# Power88.net
KiCad netlist of a schematic drawn in EAGLE
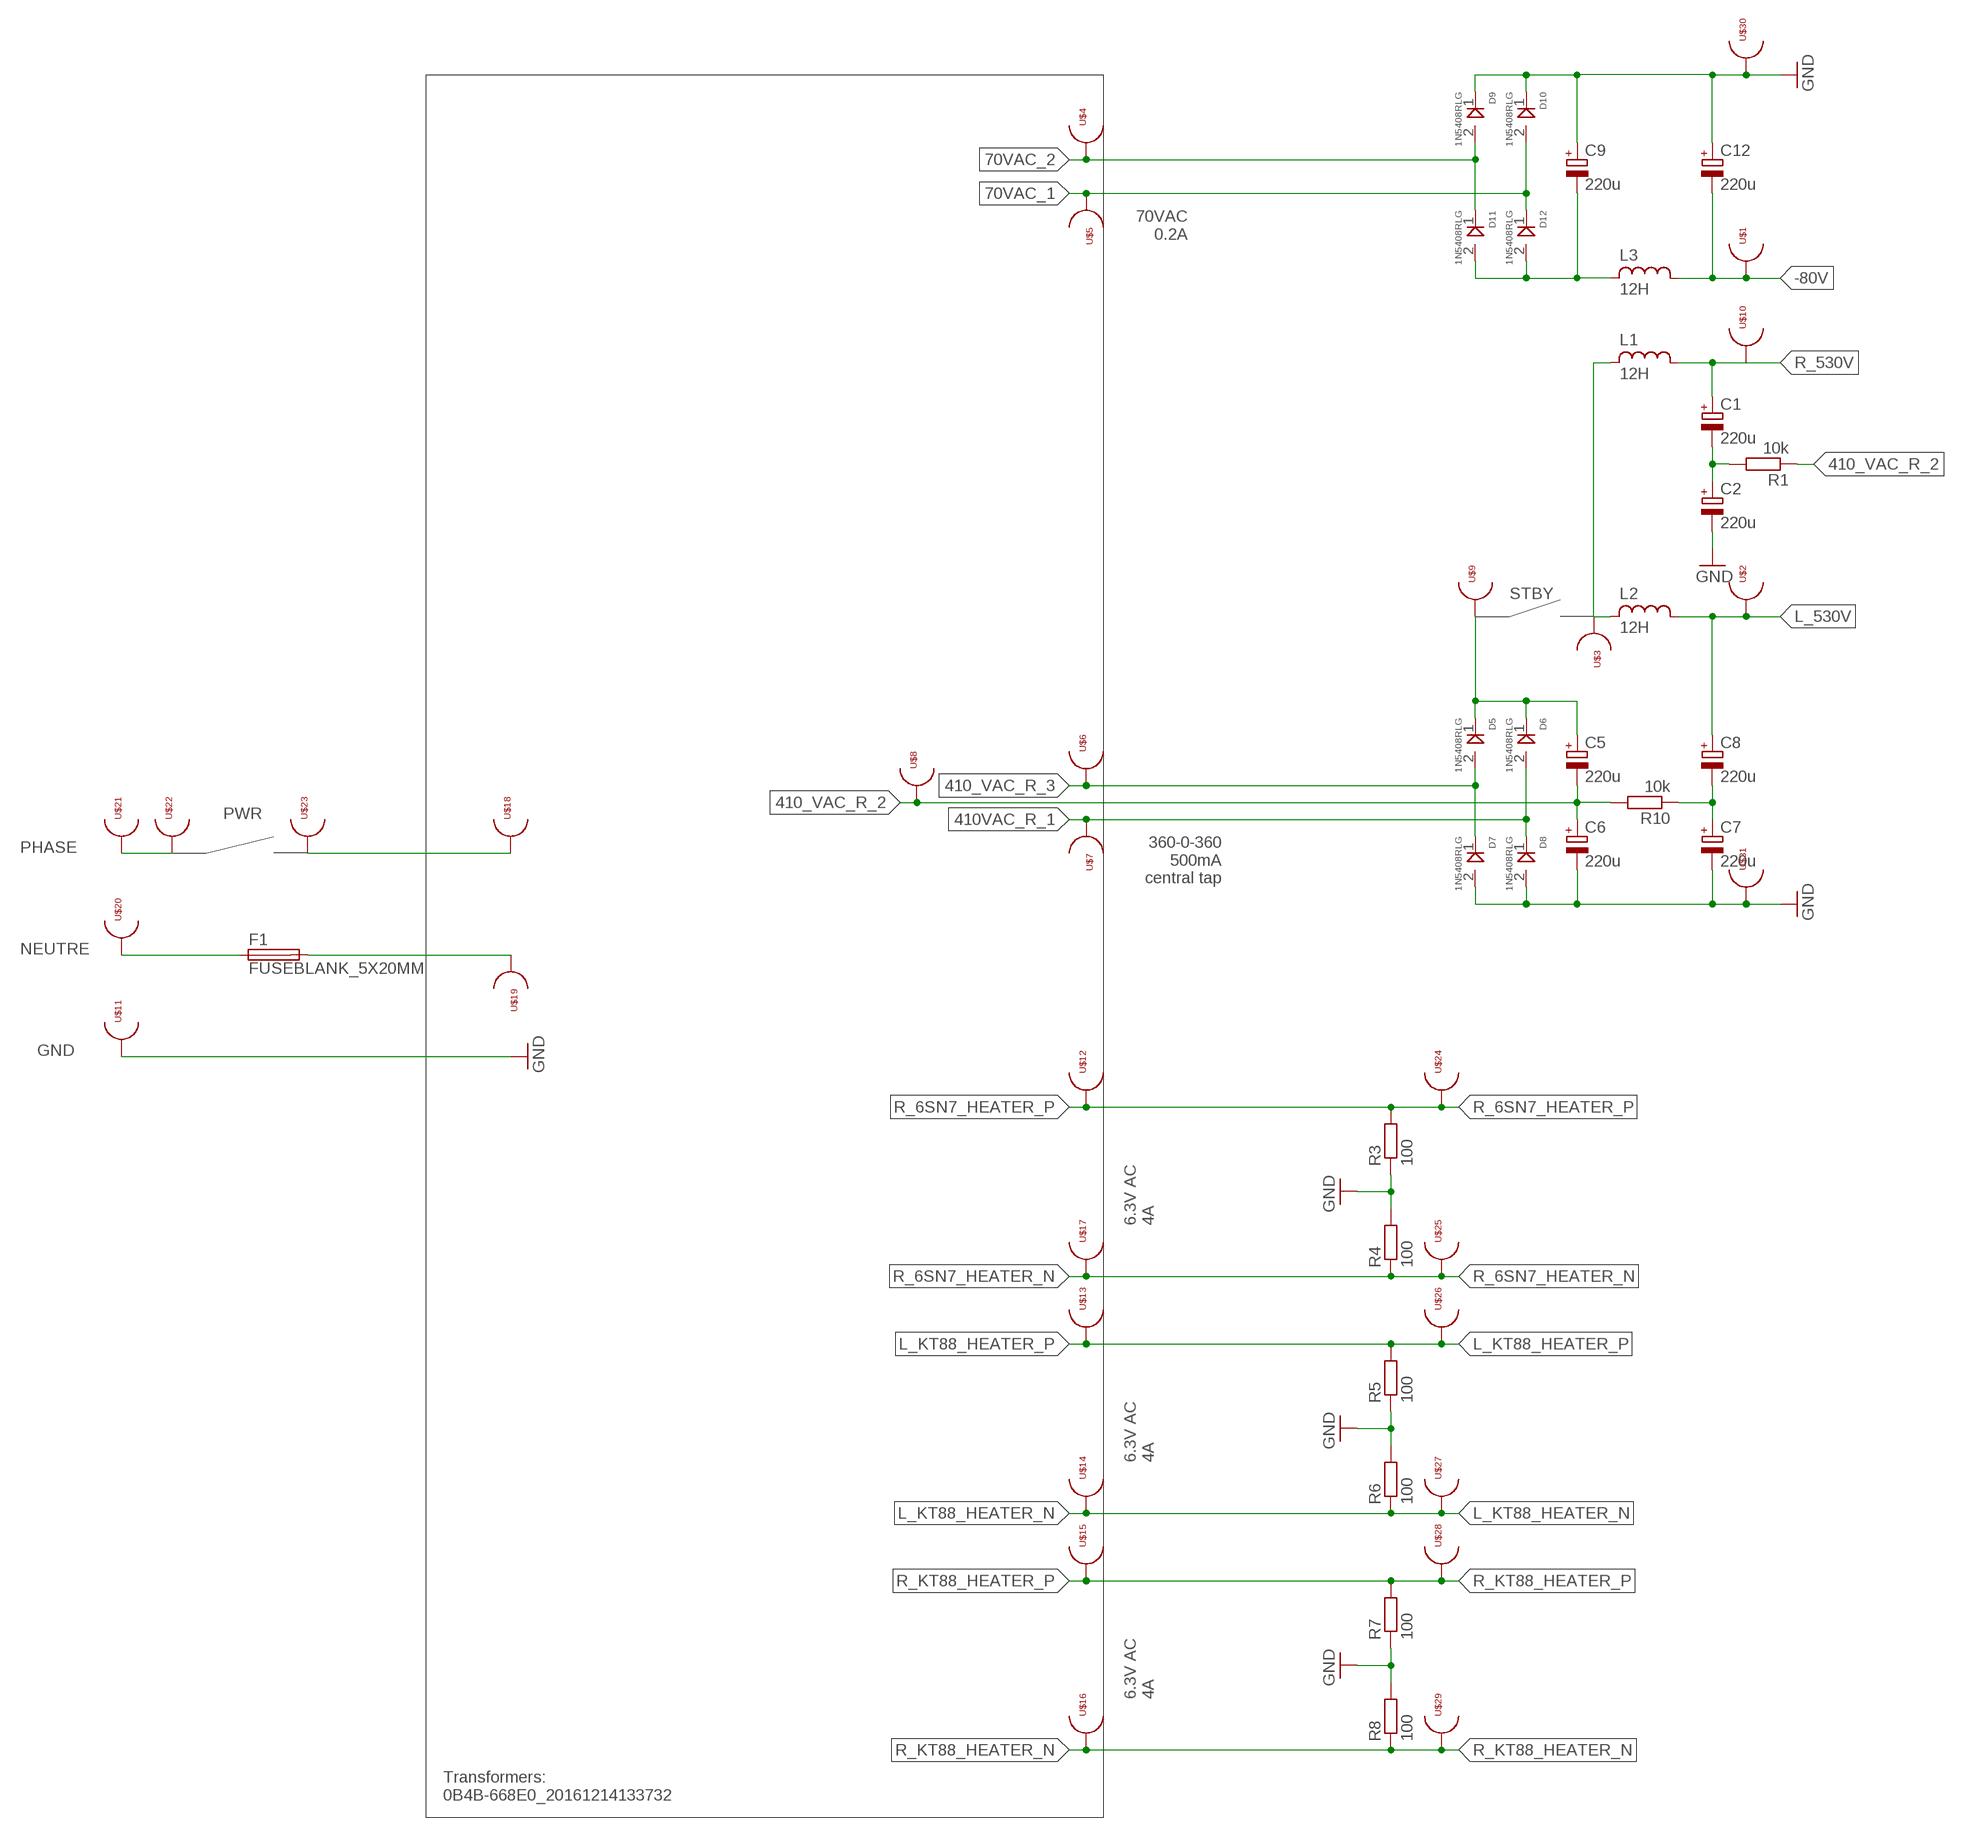
[diagram p0: schematic, sheet 1]

(export (version "E")
  (design (tool "Eeschema 10.0.6"))
  (components
    (comp (ref "C1")
      (value "220u")
      (footprint "eagle-import:E7,5-16")
      (libsource (lib "eagle-import") (part "CPOL-EUE7.5-16"))
    )
    (comp (ref "C2")
      (value "220u")
      (footprint "eagle-import:E7,5-16")
      (libsource (lib "eagle-import") (part "CPOL-EUE7.5-16"))
    )
    (comp (ref "C5")
      (value "220u")
      (footprint "eagle-import:E7,5-16")
      (libsource (lib "eagle-import") (part "CPOL-EUE7.5-16"))
    )
    (comp (ref "C6")
      (value "220u")
      (footprint "eagle-import:E7,5-16")
      (libsource (lib "eagle-import") (part "CPOL-EUE7.5-16"))
    )
    (comp (ref "C7")
      (value "220u")
      (footprint "eagle-import:E7,5-16")
      (libsource (lib "eagle-import") (part "CPOL-EUE7.5-16"))
    )
    (comp (ref "C8")
      (value "220u")
      (footprint "eagle-import:E7,5-16")
      (libsource (lib "eagle-import") (part "CPOL-EUE7.5-16"))
    )
    (comp (ref "C9")
      (value "220u")
      (footprint "eagle-import:E7,5-16")
      (libsource (lib "eagle-import") (part "CPOL-EUE7.5-16"))
    )
    (comp (ref "C12")
      (value "220u")
      (footprint "eagle-import:E7,5-16")
      (libsource (lib "eagle-import") (part "CPOL-EUE7.5-16"))
    )
    (comp (ref "D5")
      (value "1N5408RLG")
      (footprint "eagle-import:DIOAD2860W130L840D505")
      (fields (field (name "RS_PART_NUMBER") "7925322P"))
      (libsource (lib "eagle-import") (part "1N5408RLG"))
    )
    (comp (ref "D6")
      (value "1N5408RLG")
      (footprint "eagle-import:DIOAD2860W130L840D505")
      (fields (field (name "RS_PART_NUMBER") "7925322P"))
      (libsource (lib "eagle-import") (part "1N5408RLG"))
    )
    (comp (ref "D7")
      (value "1N5408RLG")
      (footprint "eagle-import:DIOAD2860W130L840D505")
      (fields (field (name "RS_PART_NUMBER") "7925322P"))
      (libsource (lib "eagle-import") (part "1N5408RLG"))
    )
    (comp (ref "D8")
      (value "1N5408RLG")
      (footprint "eagle-import:DIOAD2860W130L840D505")
      (fields (field (name "RS_PART_NUMBER") "7925322P"))
      (libsource (lib "eagle-import") (part "1N5408RLG"))
    )
    (comp (ref "D9")
      (value "1N5408RLG")
      (footprint "eagle-import:DIOAD2860W130L840D505")
      (fields (field (name "RS_PART_NUMBER") "7925322P"))
      (libsource (lib "eagle-import") (part "1N5408RLG"))
    )
    (comp (ref "D10")
      (value "1N5408RLG")
      (footprint "eagle-import:DIOAD2860W130L840D505")
      (fields (field (name "RS_PART_NUMBER") "7925322P"))
      (libsource (lib "eagle-import") (part "1N5408RLG"))
    )
    (comp (ref "D11")
      (value "1N5408RLG")
      (footprint "eagle-import:DIOAD2860W130L840D505")
      (fields (field (name "RS_PART_NUMBER") "7925322P"))
      (libsource (lib "eagle-import") (part "1N5408RLG"))
    )
    (comp (ref "D12")
      (value "1N5408RLG")
      (footprint "eagle-import:DIOAD2860W130L840D505")
      (fields (field (name "RS_PART_NUMBER") "7925322P"))
      (libsource (lib "eagle-import") (part "1N5408RLG"))
    )
    (comp (ref "F1")
      (value "FUSEBLANK_5X20MM")
      (footprint "eagle-import:FUSE_HOLDER_5X20MM")
      (libsource (lib "eagle-import") (part "FUSEBLANK_5X20MM"))
    )
    (comp (ref "L1")
      (value "12H")
      (footprint "eagle-import:RL622")
      (libsource (lib "eagle-import") (part "RL622"))
    )
    (comp (ref "L2")
      (value "12H")
      (footprint "eagle-import:RL622")
      (libsource (lib "eagle-import") (part "RL622"))
    )
    (comp (ref "L3")
      (value "12H")
      (footprint "eagle-import:RL622")
      (libsource (lib "eagle-import") (part "RL622"))
    )
    (comp (ref "R1")
      (value "10k")
      (footprint "eagle-import:R1206")
      (libsource (lib "eagle-import") (part "R-EU_R1206"))
    )
    (comp (ref "R3")
      (value "100")
      (footprint "eagle-import:R1206")
      (libsource (lib "eagle-import") (part "R-EU_R1206"))
    )
    (comp (ref "R4")
      (value "100")
      (footprint "eagle-import:R1206")
      (libsource (lib "eagle-import") (part "R-EU_R1206"))
    )
    (comp (ref "R5")
      (value "100")
      (footprint "eagle-import:R1206")
      (libsource (lib "eagle-import") (part "R-EU_R1206"))
    )
    (comp (ref "R6")
      (value "100")
      (footprint "eagle-import:R1206")
      (libsource (lib "eagle-import") (part "R-EU_R1206"))
    )
    (comp (ref "R7")
      (value "100")
      (footprint "eagle-import:R1206")
      (libsource (lib "eagle-import") (part "R-EU_R1206"))
    )
    (comp (ref "R8")
      (value "100")
      (footprint "eagle-import:R1206")
      (libsource (lib "eagle-import") (part "R-EU_R1206"))
    )
    (comp (ref "R10")
      (value "10k")
      (footprint "eagle-import:R1206")
      (libsource (lib "eagle-import") (part "R-EU_R1206"))
    )
    (comp (ref "U$1")
      (value "TESTPOINT_HOLE")
      (footprint "eagle-import:TESTPOINT_PHOLE")
      (libsource (lib "eagle-import") (part "TESTPOINT_HOLE"))
    )
    (comp (ref "U$2")
      (value "TESTPOINT_HOLE")
      (footprint "eagle-import:TESTPOINT_PHOLE")
      (libsource (lib "eagle-import") (part "TESTPOINT_HOLE"))
    )
    (comp (ref "U$3")
      (value "TESTPOINT_HOLE")
      (footprint "eagle-import:TESTPOINT_PHOLE")
      (libsource (lib "eagle-import") (part "TESTPOINT_HOLE"))
    )
    (comp (ref "U$4")
      (value "TESTPOINT_HOLE")
      (footprint "eagle-import:TESTPOINT_PHOLE")
      (libsource (lib "eagle-import") (part "TESTPOINT_HOLE"))
    )
    (comp (ref "U$5")
      (value "TESTPOINT_HOLE")
      (footprint "eagle-import:TESTPOINT_PHOLE")
      (libsource (lib "eagle-import") (part "TESTPOINT_HOLE"))
    )
    (comp (ref "U$6")
      (value "TESTPOINT_HOLE")
      (footprint "eagle-import:TESTPOINT_PHOLE")
      (libsource (lib "eagle-import") (part "TESTPOINT_HOLE"))
    )
    (comp (ref "U$7")
      (value "TESTPOINT_HOLE")
      (footprint "eagle-import:TESTPOINT_PHOLE")
      (libsource (lib "eagle-import") (part "TESTPOINT_HOLE"))
    )
    (comp (ref "U$8")
      (value "TESTPOINT_HOLE")
      (footprint "eagle-import:TESTPOINT_PHOLE")
      (libsource (lib "eagle-import") (part "TESTPOINT_HOLE"))
    )
    (comp (ref "U$9")
      (value "TESTPOINT_HOLE")
      (footprint "eagle-import:TESTPOINT_PHOLE")
      (libsource (lib "eagle-import") (part "TESTPOINT_HOLE"))
    )
    (comp (ref "U$10")
      (value "TESTPOINT_HOLE")
      (footprint "eagle-import:TESTPOINT_PHOLE")
      (libsource (lib "eagle-import") (part "TESTPOINT_HOLE"))
    )
    (comp (ref "U$11")
      (value "TESTPOINT_HOLE")
      (footprint "eagle-import:TESTPOINT_PHOLE")
      (libsource (lib "eagle-import") (part "TESTPOINT_HOLE"))
    )
    (comp (ref "U$12")
      (value "TESTPOINT_HOLE")
      (footprint "eagle-import:TESTPOINT_PHOLE")
      (libsource (lib "eagle-import") (part "TESTPOINT_HOLE"))
    )
    (comp (ref "U$13")
      (value "TESTPOINT_HOLE")
      (footprint "eagle-import:TESTPOINT_PHOLE")
      (libsource (lib "eagle-import") (part "TESTPOINT_HOLE"))
    )
    (comp (ref "U$14")
      (value "TESTPOINT_HOLE")
      (footprint "eagle-import:TESTPOINT_PHOLE")
      (libsource (lib "eagle-import") (part "TESTPOINT_HOLE"))
    )
    (comp (ref "U$15")
      (value "TESTPOINT_HOLE")
      (footprint "eagle-import:TESTPOINT_PHOLE")
      (libsource (lib "eagle-import") (part "TESTPOINT_HOLE"))
    )
    (comp (ref "U$16")
      (value "TESTPOINT_HOLE")
      (footprint "eagle-import:TESTPOINT_PHOLE")
      (libsource (lib "eagle-import") (part "TESTPOINT_HOLE"))
    )
    (comp (ref "U$17")
      (value "TESTPOINT_HOLE")
      (footprint "eagle-import:TESTPOINT_PHOLE")
      (libsource (lib "eagle-import") (part "TESTPOINT_HOLE"))
    )
    (comp (ref "U$18")
      (value "TESTPOINT_HOLE")
      (footprint "eagle-import:TESTPOINT_PHOLE")
      (libsource (lib "eagle-import") (part "TESTPOINT_HOLE"))
    )
    (comp (ref "U$19")
      (value "TESTPOINT_HOLE")
      (footprint "eagle-import:TESTPOINT_PHOLE")
      (libsource (lib "eagle-import") (part "TESTPOINT_HOLE"))
    )
    (comp (ref "U$20")
      (value "TESTPOINT_HOLE")
      (footprint "eagle-import:TESTPOINT_PHOLE")
      (libsource (lib "eagle-import") (part "TESTPOINT_HOLE"))
    )
    (comp (ref "U$21")
      (value "TESTPOINT_HOLE")
      (footprint "eagle-import:TESTPOINT_PHOLE")
      (libsource (lib "eagle-import") (part "TESTPOINT_HOLE"))
    )
    (comp (ref "U$22")
      (value "TESTPOINT_HOLE")
      (footprint "eagle-import:TESTPOINT_PHOLE")
      (libsource (lib "eagle-import") (part "TESTPOINT_HOLE"))
    )
    (comp (ref "U$23")
      (value "TESTPOINT_HOLE")
      (footprint "eagle-import:TESTPOINT_PHOLE")
      (libsource (lib "eagle-import") (part "TESTPOINT_HOLE"))
    )
    (comp (ref "U$24")
      (value "TESTPOINT_HOLE")
      (footprint "eagle-import:TESTPOINT_PHOLE")
      (libsource (lib "eagle-import") (part "TESTPOINT_HOLE"))
    )
    (comp (ref "U$25")
      (value "TESTPOINT_HOLE")
      (footprint "eagle-import:TESTPOINT_PHOLE")
      (libsource (lib "eagle-import") (part "TESTPOINT_HOLE"))
    )
    (comp (ref "U$26")
      (value "TESTPOINT_HOLE")
      (footprint "eagle-import:TESTPOINT_PHOLE")
      (libsource (lib "eagle-import") (part "TESTPOINT_HOLE"))
    )
    (comp (ref "U$27")
      (value "TESTPOINT_HOLE")
      (footprint "eagle-import:TESTPOINT_PHOLE")
      (libsource (lib "eagle-import") (part "TESTPOINT_HOLE"))
    )
    (comp (ref "U$28")
      (value "TESTPOINT_HOLE")
      (footprint "eagle-import:TESTPOINT_PHOLE")
      (libsource (lib "eagle-import") (part "TESTPOINT_HOLE"))
    )
    (comp (ref "U$29")
      (value "TESTPOINT_HOLE")
      (footprint "eagle-import:TESTPOINT_PHOLE")
      (libsource (lib "eagle-import") (part "TESTPOINT_HOLE"))
    )
    (comp (ref "U$30")
      (value "TESTPOINT_HOLE")
      (footprint "eagle-import:TESTPOINT_PHOLE")
      (libsource (lib "eagle-import") (part "TESTPOINT_HOLE"))
    )
    (comp (ref "U$31")
      (value "TESTPOINT_HOLE")
      (footprint "eagle-import:TESTPOINT_PHOLE")
      (libsource (lib "eagle-import") (part "TESTPOINT_HOLE"))
    )
  )
  (nets
    (net (code "1") (name "-80V") (class "Default")
      (node (ref "C12") (pin "-") (pinfunction "-_-") (pintype "passive"))
      (node (ref "L3") (pin "2") (pinfunction "2_2") (pintype "passive"))
      (node (ref "U$1") (pin "P$1") (pinfunction "P$1_P$1") (pintype "bidirectional"))
    )
    (net (code "2") (name "70VAC_1") (class "Default")
      (node (ref "D10") (pin "2") (pinfunction "A_2") (pintype "bidirectional"))
      (node (ref "D12") (pin "1") (pinfunction "K_1") (pintype "bidirectional"))
      (node (ref "U$5") (pin "P$1") (pinfunction "P$1_P$1") (pintype "bidirectional"))
    )
    (net (code "3") (name "70VAC_2") (class "Default")
      (node (ref "D11") (pin "1") (pinfunction "K_1") (pintype "bidirectional"))
      (node (ref "D9") (pin "2") (pinfunction "A_2") (pintype "bidirectional"))
      (node (ref "U$4") (pin "P$1") (pinfunction "P$1_P$1") (pintype "bidirectional"))
    )
    (net (code "4") (name "410VAC_R_1") (class "Default")
      (node (ref "D6") (pin "2") (pinfunction "A_2") (pintype "bidirectional"))
      (node (ref "D8") (pin "1") (pinfunction "K_1") (pintype "bidirectional"))
      (node (ref "U$7") (pin "P$1") (pinfunction "P$1_P$1") (pintype "bidirectional"))
    )
    (net (code "5") (name "410_VAC_R_2") (class "Default")
      (node (ref "C5") (pin "-") (pinfunction "-_-") (pintype "passive"))
      (node (ref "C6") (pin "+") (pinfunction "+_+") (pintype "passive"))
      (node (ref "R1") (pin "1") (pinfunction "1_1") (pintype "passive"))
      (node (ref "R10") (pin "2") (pinfunction "2_2") (pintype "passive"))
      (node (ref "U$8") (pin "P$1") (pinfunction "P$1_P$1") (pintype "bidirectional"))
    )
    (net (code "6") (name "410_VAC_R_3") (class "Default")
      (node (ref "D5") (pin "2") (pinfunction "A_2") (pintype "bidirectional"))
      (node (ref "D7") (pin "1") (pinfunction "K_1") (pintype "bidirectional"))
      (node (ref "U$6") (pin "P$1") (pinfunction "P$1_P$1") (pintype "bidirectional"))
    )
    (net (code "7") (name "GND") (class "Default")
      (node (ref "C12") (pin "+") (pinfunction "+_+") (pintype "passive"))
      (node (ref "C2") (pin "-") (pinfunction "-_-") (pintype "passive"))
      (node (ref "C6") (pin "-") (pinfunction "-_-") (pintype "passive"))
      (node (ref "C7") (pin "-") (pinfunction "-_-") (pintype "passive"))
      (node (ref "C9") (pin "+") (pinfunction "+_+") (pintype "passive"))
      (node (ref "D10") (pin "1") (pinfunction "K_1") (pintype "bidirectional"))
      (node (ref "D7") (pin "2") (pinfunction "A_2") (pintype "bidirectional"))
      (node (ref "D8") (pin "2") (pinfunction "A_2") (pintype "bidirectional"))
      (node (ref "D9") (pin "1") (pinfunction "K_1") (pintype "bidirectional"))
      (node (ref "R3") (pin "1") (pinfunction "1_1") (pintype "passive"))
      (node (ref "R4") (pin "2") (pinfunction "2_2") (pintype "passive"))
      (node (ref "R5") (pin "1") (pinfunction "1_1") (pintype "passive"))
      (node (ref "R6") (pin "2") (pinfunction "2_2") (pintype "passive"))
      (node (ref "R7") (pin "1") (pinfunction "1_1") (pintype "passive"))
      (node (ref "R8") (pin "2") (pinfunction "2_2") (pintype "passive"))
      (node (ref "U$11") (pin "P$1") (pinfunction "P$1_P$1") (pintype "bidirectional"))
      (node (ref "U$30") (pin "P$1") (pinfunction "P$1_P$1") (pintype "bidirectional"))
      (node (ref "U$31") (pin "P$1") (pinfunction "P$1_P$1") (pintype "bidirectional"))
    )
    (net (code "8") (name "L_530V") (class "Default")
      (node (ref "C8") (pin "+") (pinfunction "+_+") (pintype "passive"))
      (node (ref "L2") (pin "2") (pinfunction "2_2") (pintype "passive"))
      (node (ref "U$2") (pin "P$1") (pinfunction "P$1_P$1") (pintype "bidirectional"))
    )
    (net (code "9") (name "L_KT88_HEATER_N") (class "Default")
      (node (ref "R6") (pin "1") (pinfunction "1_1") (pintype "passive"))
      (node (ref "U$14") (pin "P$1") (pinfunction "P$1_P$1") (pintype "bidirectional"))
      (node (ref "U$27") (pin "P$1") (pinfunction "P$1_P$1") (pintype "bidirectional"))
    )
    (net (code "10") (name "L_KT88_HEATER_P") (class "Default")
      (node (ref "R5") (pin "2") (pinfunction "2_2") (pintype "passive"))
      (node (ref "U$13") (pin "P$1") (pinfunction "P$1_P$1") (pintype "bidirectional"))
      (node (ref "U$26") (pin "P$1") (pinfunction "P$1_P$1") (pintype "bidirectional"))
    )
    (net (code "11") (name "Net-(C1-Pad-)") (class "Default")
      (node (ref "C1") (pin "-") (pinfunction "-_-") (pintype "passive"))
      (node (ref "C2") (pin "+") (pinfunction "+_+") (pintype "passive"))
      (node (ref "R1") (pin "2") (pinfunction "2_2") (pintype "passive"))
    )
    (net (code "12") (name "Net-(C7-Pad+)") (class "Default")
      (node (ref "C7") (pin "+") (pinfunction "+_+") (pintype "passive"))
      (node (ref "C8") (pin "-") (pinfunction "-_-") (pintype "passive"))
      (node (ref "R10") (pin "1") (pinfunction "1_1") (pintype "passive"))
    )
    (net (code "13") (name "Net-(D5-K)") (class "Default")
      (node (ref "C5") (pin "+") (pinfunction "+_+") (pintype "passive"))
      (node (ref "D5") (pin "1") (pinfunction "K_1") (pintype "bidirectional"))
      (node (ref "D6") (pin "1") (pinfunction "K_1") (pintype "bidirectional"))
      (node (ref "U$9") (pin "P$1") (pinfunction "P$1_P$1") (pintype "bidirectional"))
    )
    (net (code "14") (name "Net-(D11-A)") (class "Default")
      (node (ref "C9") (pin "-") (pinfunction "-_-") (pintype "passive"))
      (node (ref "D11") (pin "2") (pinfunction "A_2") (pintype "bidirectional"))
      (node (ref "D12") (pin "2") (pinfunction "A_2") (pintype "bidirectional"))
      (node (ref "L3") (pin "1") (pinfunction "1_1") (pintype "passive"))
    )
    (net (code "15") (name "Net-(F1-Pad1)") (class "Default")
      (node (ref "F1") (pin "1") (pinfunction "1_1") (pintype "passive"))
      (node (ref "U$20") (pin "P$1") (pinfunction "P$1_P$1") (pintype "bidirectional"))
    )
    (net (code "16") (name "Net-(F1-Pad2)") (class "Default")
      (node (ref "F1") (pin "2") (pinfunction "2_2") (pintype "passive"))
      (node (ref "U$19") (pin "P$1") (pinfunction "P$1_P$1") (pintype "bidirectional"))
    )
    (net (code "17") (name "Net-(L1-Pad1)") (class "Default")
      (node (ref "L1") (pin "1") (pinfunction "1_1") (pintype "passive"))
      (node (ref "L2") (pin "1") (pinfunction "1_1") (pintype "passive"))
      (node (ref "U$3") (pin "P$1") (pinfunction "P$1_P$1") (pintype "bidirectional"))
    )
    (net (code "18") (name "Net-(U$18-PadP$1)") (class "Default")
      (node (ref "U$18") (pin "P$1") (pinfunction "P$1_P$1") (pintype "bidirectional"))
      (node (ref "U$23") (pin "P$1") (pinfunction "P$1_P$1") (pintype "bidirectional"))
    )
    (net (code "19") (name "Net-(U$21-PadP$1)") (class "Default")
      (node (ref "U$21") (pin "P$1") (pinfunction "P$1_P$1") (pintype "bidirectional"))
      (node (ref "U$22") (pin "P$1") (pinfunction "P$1_P$1") (pintype "bidirectional"))
    )
    (net (code "20") (name "R_6SN7_HEATER_N") (class "Default")
      (node (ref "R4") (pin "1") (pinfunction "1_1") (pintype "passive"))
      (node (ref "U$17") (pin "P$1") (pinfunction "P$1_P$1") (pintype "bidirectional"))
      (node (ref "U$25") (pin "P$1") (pinfunction "P$1_P$1") (pintype "bidirectional"))
    )
    (net (code "21") (name "R_6SN7_HEATER_P") (class "Default")
      (node (ref "R3") (pin "2") (pinfunction "2_2") (pintype "passive"))
      (node (ref "U$12") (pin "P$1") (pinfunction "P$1_P$1") (pintype "bidirectional"))
      (node (ref "U$24") (pin "P$1") (pinfunction "P$1_P$1") (pintype "bidirectional"))
    )
    (net (code "22") (name "R_530V") (class "Default")
      (node (ref "C1") (pin "+") (pinfunction "+_+") (pintype "passive"))
      (node (ref "L1") (pin "2") (pinfunction "2_2") (pintype "passive"))
      (node (ref "U$10") (pin "P$1") (pinfunction "P$1_P$1") (pintype "bidirectional"))
    )
    (net (code "23") (name "R_KT88_HEATER_N") (class "Default")
      (node (ref "R8") (pin "1") (pinfunction "1_1") (pintype "passive"))
      (node (ref "U$16") (pin "P$1") (pinfunction "P$1_P$1") (pintype "bidirectional"))
      (node (ref "U$29") (pin "P$1") (pinfunction "P$1_P$1") (pintype "bidirectional"))
    )
    (net (code "24") (name "R_KT88_HEATER_P") (class "Default")
      (node (ref "R7") (pin "2") (pinfunction "2_2") (pintype "passive"))
      (node (ref "U$15") (pin "P$1") (pinfunction "P$1_P$1") (pintype "bidirectional"))
      (node (ref "U$28") (pin "P$1") (pinfunction "P$1_P$1") (pintype "bidirectional"))
    )
  )
)
